# Coolant_Relays.net
KiCad netlist of a schematic drawn in Altium Designer
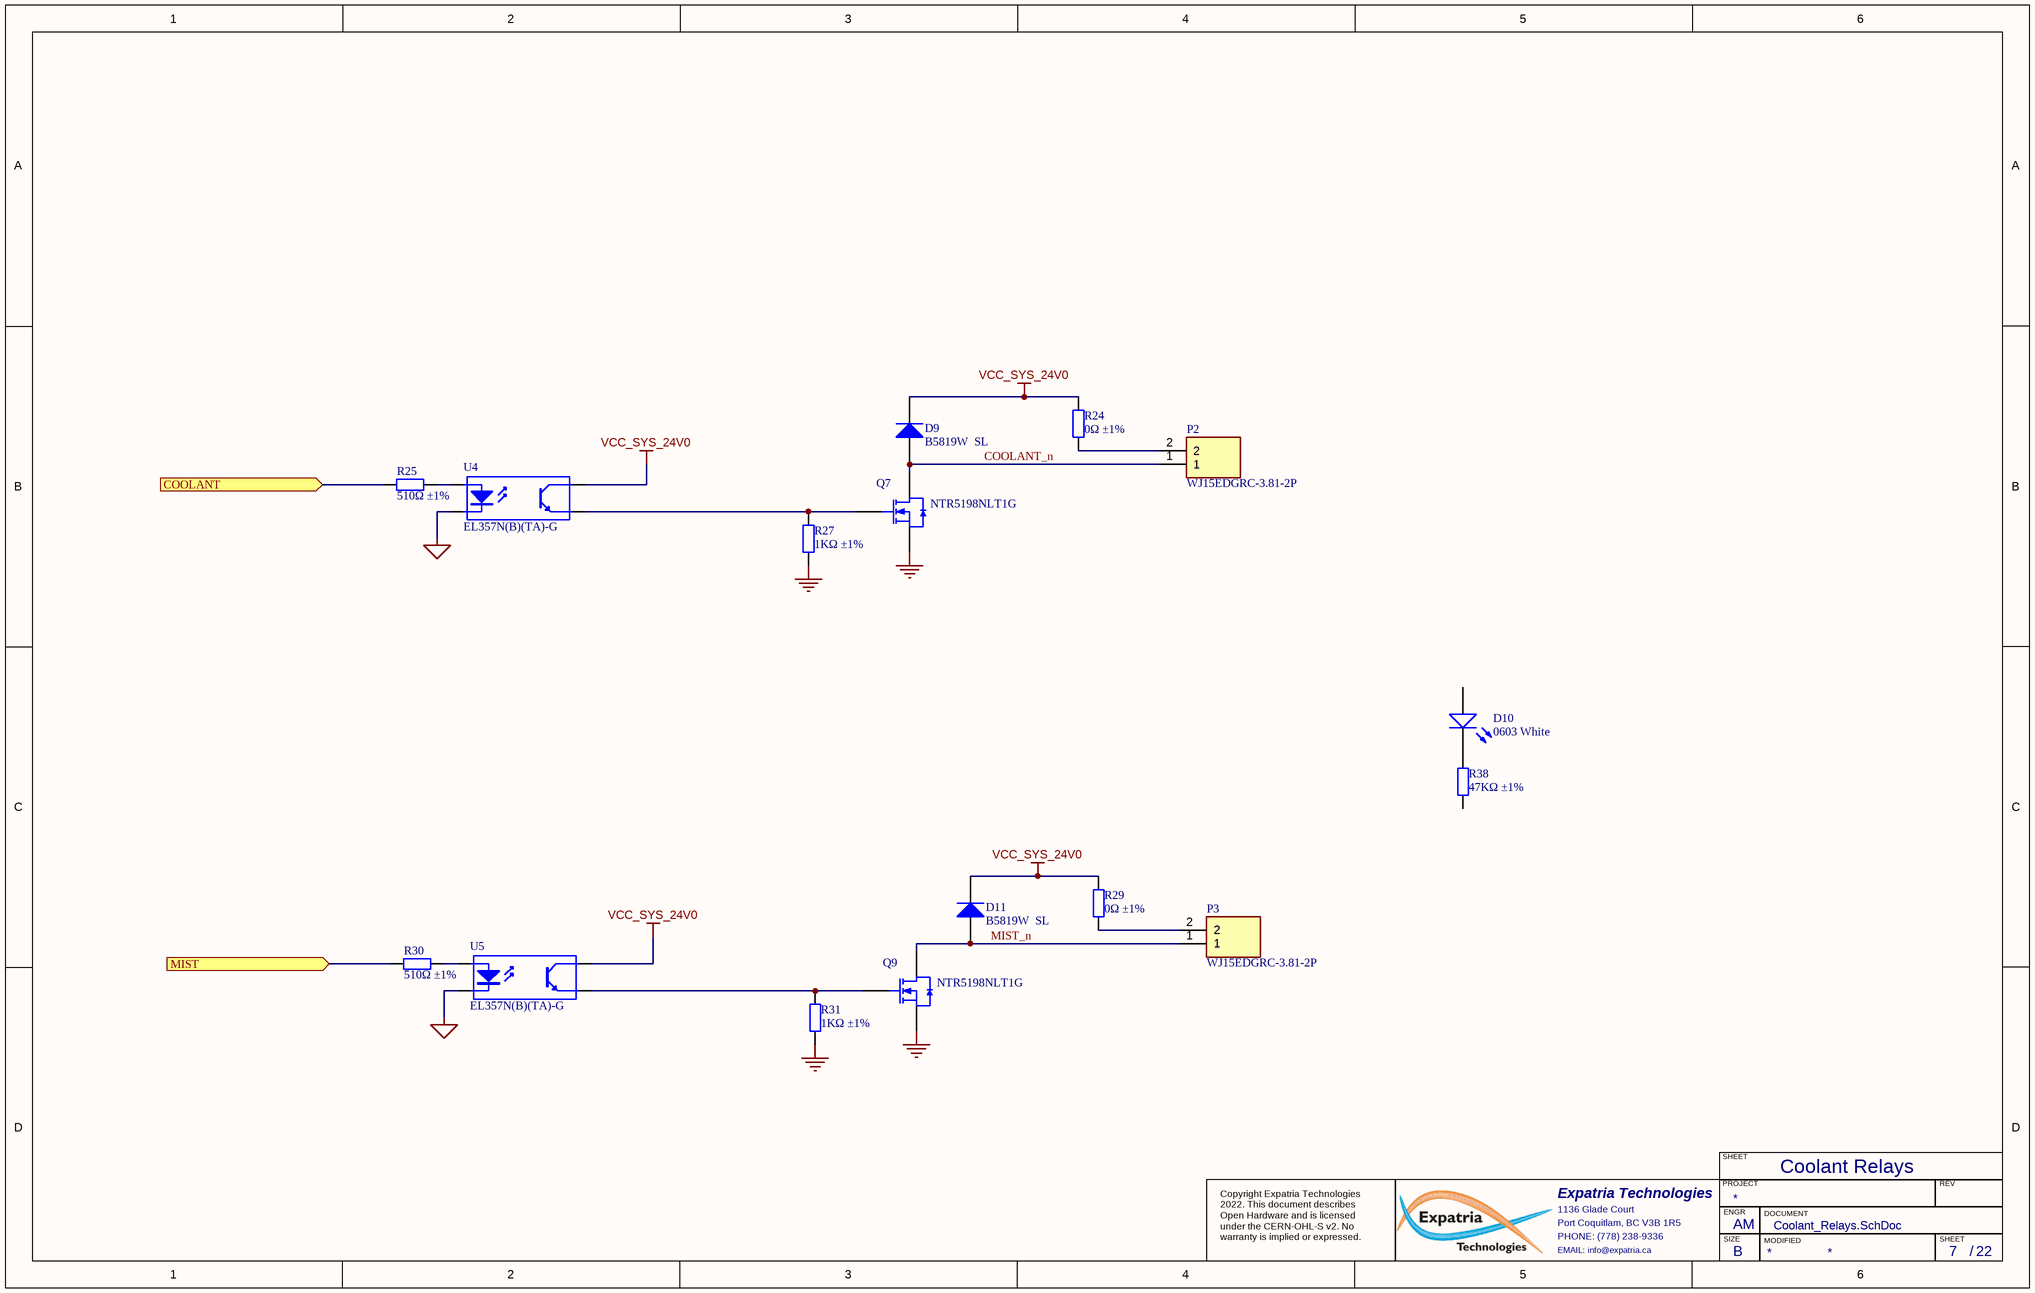
[diagram p0: Coolant_Relays.SchDoc]

(export (version "E")
  (design (tool "Eeschema 10.0.6"))
  (components
    (comp (ref "D9")
      (value "B5819W  SL")
      (footprint "SOD-123")
      (description "Schottky Diode")
      (libsource (lib "Diode") (part "SOD-123 B5819W  SL"))
    )
    (comp (ref "D10")
      (value "0603 White")
      (footprint "0603_LED_S1")
      (description "LED")
      (libsource (lib "Sienci_Labs") (part "19-217UWD/S365-2/TR8"))
    )
    (comp (ref "D11")
      (value "B5819W  SL")
      (footprint "SOD-123")
      (description "Schottky Diode")
      (libsource (lib "Diode") (part "SOD-123 B5819W  SL"))
    )
    (comp (ref "P2")
      (value "WJ15EDGRC-3.81-2P")
      (footprint "SHDRRA2W85P0X381_1X2_850X915X720P")
      (description "3.81mm Green Board Edge/Receptacle-Close Push-Pull,P=3.81mm Pluggable System Terminal Block ROHS")
      (libsource (lib "Sienci_Labs") (part "WJ15EDGRC-3.81-2P"))
    )
    (comp (ref "P3")
      (value "WJ15EDGRC-3.81-2P")
      (footprint "SHDRRA2W85P0X381_1X2_850X915X720P")
      (description "3.81mm Green Board Edge/Receptacle-Close Push-Pull,P=3.81mm Pluggable System Terminal Block ROHS")
      (libsource (lib "Sienci_Labs") (part "WJ15EDGRC-3.81-2P"))
    )
    (comp (ref "Q7")
      (value "NTR5198NLT1G")
      (footprint "SOT-23-3L")
      (description "60V 1.7A 155mΩ@10V,1A 900mW 2.5V@250uA N Channel SOT-23(SOT-23-3) MOSFETs ROHS")
      (libsource (lib "Sienci_Labs") (part "AO3400A"))
    )
    (comp (ref "Q9")
      (value "NTR5198NLT1G")
      (footprint "SOT-23-3L")
      (description "60V 1.7A 155mΩ@10V,1A 900mW 2.5V@250uA N Channel SOT-23(SOT-23-3) MOSFETs ROHS")
      (libsource (lib "Sienci_Labs") (part "AO3400A"))
    )
    (comp (ref "R24")
      (value "0Ω ±1%")
      (footprint "0603_R")
      (description "Chip resistor")
      (fields (field (name "MANUFACTURER") "Uniroyal Elec") (field (name "PARTNUMBER") "0603WAF0000T5E"))
      (libsource (lib "RES") (part "0603 0R (0R0) 1%"))
    )
    (comp (ref "R25")
      (value "510Ω ±1%")
      (footprint "0603_R")
      (description "Chip resistor")
      (fields (field (name "MANUFACTURER") "Uniroyal Elec") (field (name "PARTNUMBER") "0603WAF5100T5E"))
      (libsource (lib "RES") (part "0603 510R (5100) 1%"))
    )
    (comp (ref "R27")
      (value "1KΩ ±1%")
      (footprint "0603_R")
      (description "Chip resistor")
      (fields (field (name "MANUFACTURER") "Uniroyal Elec") (field (name "PARTNUMBER") "0603WAF1001T5E"))
      (libsource (lib "RES") (part "0603 1K (1001) 1%"))
    )
    (comp (ref "R29")
      (value "0Ω ±1%")
      (footprint "0603_R")
      (description "Chip resistor")
      (fields (field (name "MANUFACTURER") "Uniroyal Elec") (field (name "PARTNUMBER") "0603WAF0000T5E"))
      (libsource (lib "RES") (part "0603 0R (0R0) 1%"))
    )
    (comp (ref "R30")
      (value "510Ω ±1%")
      (footprint "0603_R")
      (description "Chip resistor")
      (fields (field (name "MANUFACTURER") "Uniroyal Elec") (field (name "PARTNUMBER") "0603WAF5100T5E"))
      (libsource (lib "RES") (part "0603 510R (5100) 1%"))
    )
    (comp (ref "R31")
      (value "1KΩ ±1%")
      (footprint "0603_R")
      (description "Chip resistor")
      (fields (field (name "MANUFACTURER") "Uniroyal Elec") (field (name "PARTNUMBER") "0603WAF1001T5E"))
      (libsource (lib "RES") (part "0603 1K (1001) 1%"))
    )
    (comp (ref "R38")
      (value "47KΩ ±1%")
      (footprint "0603_R")
      (description "Chip resistor")
      (fields (field (name "MANUFACTURER") "Uniroyal Elec") (field (name "PARTNUMBER") "0603WAF4702T5E"))
      (libsource (lib "RES") (part "0603 47K (4702) 1%"))
    )
    (comp (ref "U4")
      (value "EL357N(B)(TA)-G")
      (footprint "Miscellaneous Devices LC:SOP-4_P2.54")
      (description "OPTOISOLATOR 3.75KV TRANS 4-SOP")
      (libsource (lib "IC") (part "EL357N(B)(TA)-G_[C6649]"))
    )
    (comp (ref "U5")
      (value "EL357N(B)(TA)-G")
      (footprint "Miscellaneous Devices LC:SOP-4_P2.54")
      (description "OPTOISOLATOR 3.75KV TRANS 4-SOP")
      (libsource (lib "IC") (part "EL357N(B)(TA)-G_[C6649]"))
    )
  )
  (nets
    (net (code "1") (name "/COOLANT") (class "Default")
      (node (ref "R25") (pin "1") (pinfunction "1_1") (pintype "passive"))
    )
    (net (code "2") (name "/COOLANT_n") (class "Default")
      (node (ref "D9") (pin "1") (pinfunction "A_1") (pintype "passive"))
      (node (ref "P2") (pin "1") (pinfunction "1_1") (pintype "passive"))
      (node (ref "Q7") (pin "3") (pinfunction "D_3") (pintype "passive"))
    )
    (net (code "3") (name "/MIST") (class "Default")
      (node (ref "R30") (pin "1") (pinfunction "1_1") (pintype "passive"))
    )
    (net (code "4") (name "/MIST_n") (class "Default")
      (node (ref "D11") (pin "1") (pinfunction "A_1") (pintype "passive"))
      (node (ref "P3") (pin "1") (pinfunction "1_1") (pintype "passive"))
      (node (ref "Q9") (pin "3") (pinfunction "D_3") (pintype "passive"))
    )
    (net (code "5") (name "GND") (class "Default")
      (node (ref "Q7") (pin "2") (pinfunction "S_2") (pintype "passive"))
      (node (ref "Q9") (pin "2") (pinfunction "S_2") (pintype "passive"))
      (node (ref "R27") (pin "1") (pinfunction "1_1") (pintype "passive"))
      (node (ref "R31") (pin "1") (pinfunction "1_1") (pintype "passive"))
    )
    (net (code "6") (name "MCU_GND") (class "Default")
      (node (ref "U4") (pin "2") (pinfunction "K_2") (pintype "passive"))
      (node (ref "U5") (pin "2") (pinfunction "K_2") (pintype "passive"))
    )
    (net (code "7") (name "Net-(D10-PadK)") (class "Default")
      (node (ref "D10") (pin "K") (pinfunction "K_K") (pintype "passive"))
      (node (ref "R38") (pin "2") (pinfunction "2_2") (pintype "passive"))
    )
    (net (code "8") (name "Net-(P2-Pad2)") (class "Default")
      (node (ref "P2") (pin "2") (pinfunction "2_2") (pintype "passive"))
      (node (ref "R24") (pin "2") (pinfunction "2_2") (pintype "passive"))
    )
    (net (code "9") (name "Net-(P3-Pad2)") (class "Default")
      (node (ref "P3") (pin "2") (pinfunction "2_2") (pintype "passive"))
      (node (ref "R29") (pin "2") (pinfunction "2_2") (pintype "passive"))
    )
    (net (code "10") (name "Net-(Q7-G)") (class "Default")
      (node (ref "Q7") (pin "1") (pinfunction "G_1") (pintype "passive"))
      (node (ref "R27") (pin "2") (pinfunction "2_2") (pintype "passive"))
      (node (ref "U4") (pin "3") (pinfunction "E_3") (pintype "passive"))
    )
    (net (code "11") (name "Net-(Q9-G)") (class "Default")
      (node (ref "Q9") (pin "1") (pinfunction "G_1") (pintype "passive"))
      (node (ref "R31") (pin "2") (pinfunction "2_2") (pintype "passive"))
      (node (ref "U5") (pin "3") (pinfunction "E_3") (pintype "passive"))
    )
    (net (code "12") (name "Net-(U4-A)") (class "Default")
      (node (ref "R25") (pin "2") (pinfunction "2_2") (pintype "passive"))
      (node (ref "U4") (pin "1") (pinfunction "A_1") (pintype "passive"))
    )
    (net (code "13") (name "Net-(U5-A)") (class "Default")
      (node (ref "R30") (pin "2") (pinfunction "2_2") (pintype "passive"))
      (node (ref "U5") (pin "1") (pinfunction "A_1") (pintype "passive"))
    )
    (net (code "14") (name "VCC_SYS_24V0") (class "Default")
      (node (ref "D11") (pin "2") (pinfunction "K_2") (pintype "passive"))
      (node (ref "D9") (pin "2") (pinfunction "K_2") (pintype "passive"))
      (node (ref "R24") (pin "1") (pinfunction "1_1") (pintype "passive"))
      (node (ref "R29") (pin "1") (pinfunction "1_1") (pintype "passive"))
      (node (ref "U4") (pin "4") (pinfunction "C_4") (pintype "passive"))
      (node (ref "U5") (pin "4") (pinfunction "C_4") (pintype "passive"))
    )
    (net (code "15") (name "unconnected-(D10-PadA)") (class "Default")
      (node (ref "D10") (pin "A") (pinfunction "A_A") (pintype "passive"))
    )
    (net (code "16") (name "unconnected-(R38-Pad1)") (class "Default")
      (node (ref "R38") (pin "1") (pinfunction "1_1") (pintype "passive"))
    )
  )
)
